# Sensor.net
KiCad netlist of a schematic drawn in Altium Designer
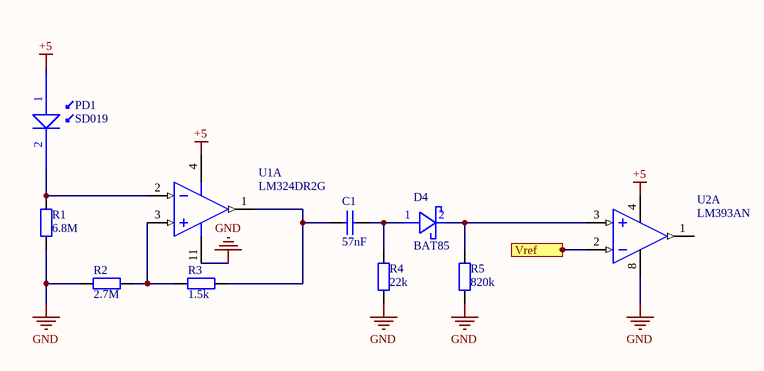
[diagram p0: Sensor.SchDoc]

(export (version "E")
  (design (tool "Eeschema 10.0.6"))
  (components
    (comp (ref "C1")
      (value "57nF")
      (footprint "0805 CAP")
      (description "SMT ceramic capacitor 0805 size")
      (libsource (lib "EE209_Library") (part "CerCap_SMT_0805"))
    )
    (comp (ref "D4") (value "BAT85") (footprint "BAT85") (libsource (lib "301") (part "BAT85")))
    (comp (ref "PD1") (value "SD019") (footprint "SD019") (libsource (lib "301") (part "SD019")))
    (comp (ref "R1")
      (value "6.8M")
      (footprint "0805 RES")
      (description "0805 resistor")
      (fields (field (name "PUBLISHER") "Altium Limited"))
      (libsource (lib "") (part "Res_SMT_0805_2"))
    )
    (comp (ref "R2")
      (value "2.7M")
      (footprint "0805 RES")
      (description "0805 resistor")
      (fields (field (name "PUBLISHER") "Altium Limited"))
      (libsource (lib "") (part "Res_SMT_0805_1"))
    )
    (comp (ref "R3")
      (value "1.5k")
      (footprint "0805 RES")
      (description "0805 resistor")
      (fields (field (name "PUBLISHER") "Altium Limited"))
      (libsource (lib "EE209_Library") (part "Res_SMT_0805"))
    )
    (comp (ref "R4")
      (value "22k")
      (footprint "0805 RES")
      (description "0805 resistor")
      (fields (field (name "PUBLISHER") "Altium Limited"))
      (libsource (lib "") (part "Res_SMT_0805_2"))
    )
    (comp (ref "R5")
      (value "820k")
      (footprint "0805 RES")
      (description "0805 resistor")
      (fields (field (name "PUBLISHER") "Altium Limited"))
      (libsource (lib "") (part "Res_SMT_0805_2"))
    )
    (comp (ref "U1")
      (value "LM324DR2G")
      (footprint "SOIC-14")
      (fields (field (name "MANUFACTURER") "On Semiconductor"))
      (libsource (lib "EE209_Library") (part "LM324DR_SMT_SOIC16"))
    )
    (comp (ref "U2")
      (value "LM393AN")
      (footprint "ECE-DIP8")
      (description "Dual Comparator")
      (fields (field (name "PUBLISHER") "Altium Limited"))
      (libsource (lib "ece components") (part "LM393AN"))
    )
  )
  (nets
    (net (code "1") (name "+5") (class "Default")
      (node (ref "PD1") (pin "1") (pintype "passive"))
      (node (ref "U1") (pin "4") (pinfunction "VCC_4") (pintype "power_in"))
      (node (ref "U2") (pin "4") (pinfunction "GND_4") (pintype "power_in"))
    )
    (net (code "2") (name "/Vref") (class "Default")
      (node (ref "U2") (pin "2") (pinfunction "IN-_2") (pintype "input"))
    )
    (net (code "3") (name "GND") (class "Default")
      (node (ref "R1") (pin "1") (pinfunction "1_1") (pintype "passive"))
      (node (ref "R2") (pin "2") (pinfunction "2_2") (pintype "passive"))
      (node (ref "R4") (pin "1") (pinfunction "1_1") (pintype "passive"))
      (node (ref "R5") (pin "1") (pinfunction "1_1") (pintype "passive"))
      (node (ref "U1") (pin "11") (pinfunction "VEE/GND_11") (pintype "power_in"))
      (node (ref "U2") (pin "8") (pinfunction "V+_8") (pintype "power_in"))
    )
    (net (code "4") (name "Net-(C1-Pad2)") (class "Default")
      (node (ref "C1") (pin "2") (pinfunction "2_2") (pintype "passive"))
      (node (ref "D4") (pin "1") (pintype "passive"))
      (node (ref "R4") (pin "2") (pinfunction "2_2") (pintype "passive"))
    )
    (net (code "5") (name "Net-(U1A-IN1+)") (class "Default")
      (node (ref "R2") (pin "1") (pinfunction "1_1") (pintype "passive"))
      (node (ref "R3") (pin "1") (pinfunction "1_1") (pintype "passive"))
      (node (ref "U1") (pin "3") (pinfunction "IN1+_3") (pintype "input"))
    )
    (net (code "6") (name "Net-(U1A-IN1-)") (class "Default")
      (node (ref "PD1") (pin "2") (pintype "passive"))
      (node (ref "R1") (pin "2") (pinfunction "2_2") (pintype "passive"))
      (node (ref "U1") (pin "2") (pinfunction "IN1-_2") (pintype "input"))
    )
    (net (code "7") (name "Net-(U1A-OUT1)") (class "Default")
      (node (ref "C1") (pin "1") (pinfunction "1_1") (pintype "passive"))
      (node (ref "R3") (pin "2") (pinfunction "2_2") (pintype "passive"))
      (node (ref "U1") (pin "1") (pinfunction "OUT1_1") (pintype "output"))
    )
    (net (code "8") (name "Net-(U2A-IN+)") (class "Default")
      (node (ref "D4") (pin "2") (pintype "passive"))
      (node (ref "R5") (pin "2") (pinfunction "2_2") (pintype "passive"))
      (node (ref "U2") (pin "3") (pinfunction "IN+_3") (pintype "input"))
    )
    (net (code "9") (name "unconnected-(U2A-OUT-Pad1)") (class "Default")
      (node (ref "U2") (pin "1") (pinfunction "OUT_1") (pintype "output"))
    )
  )
)
